# boost-demux_v1_1.net
KiCad netlist of a schematic drawn in EAGLE
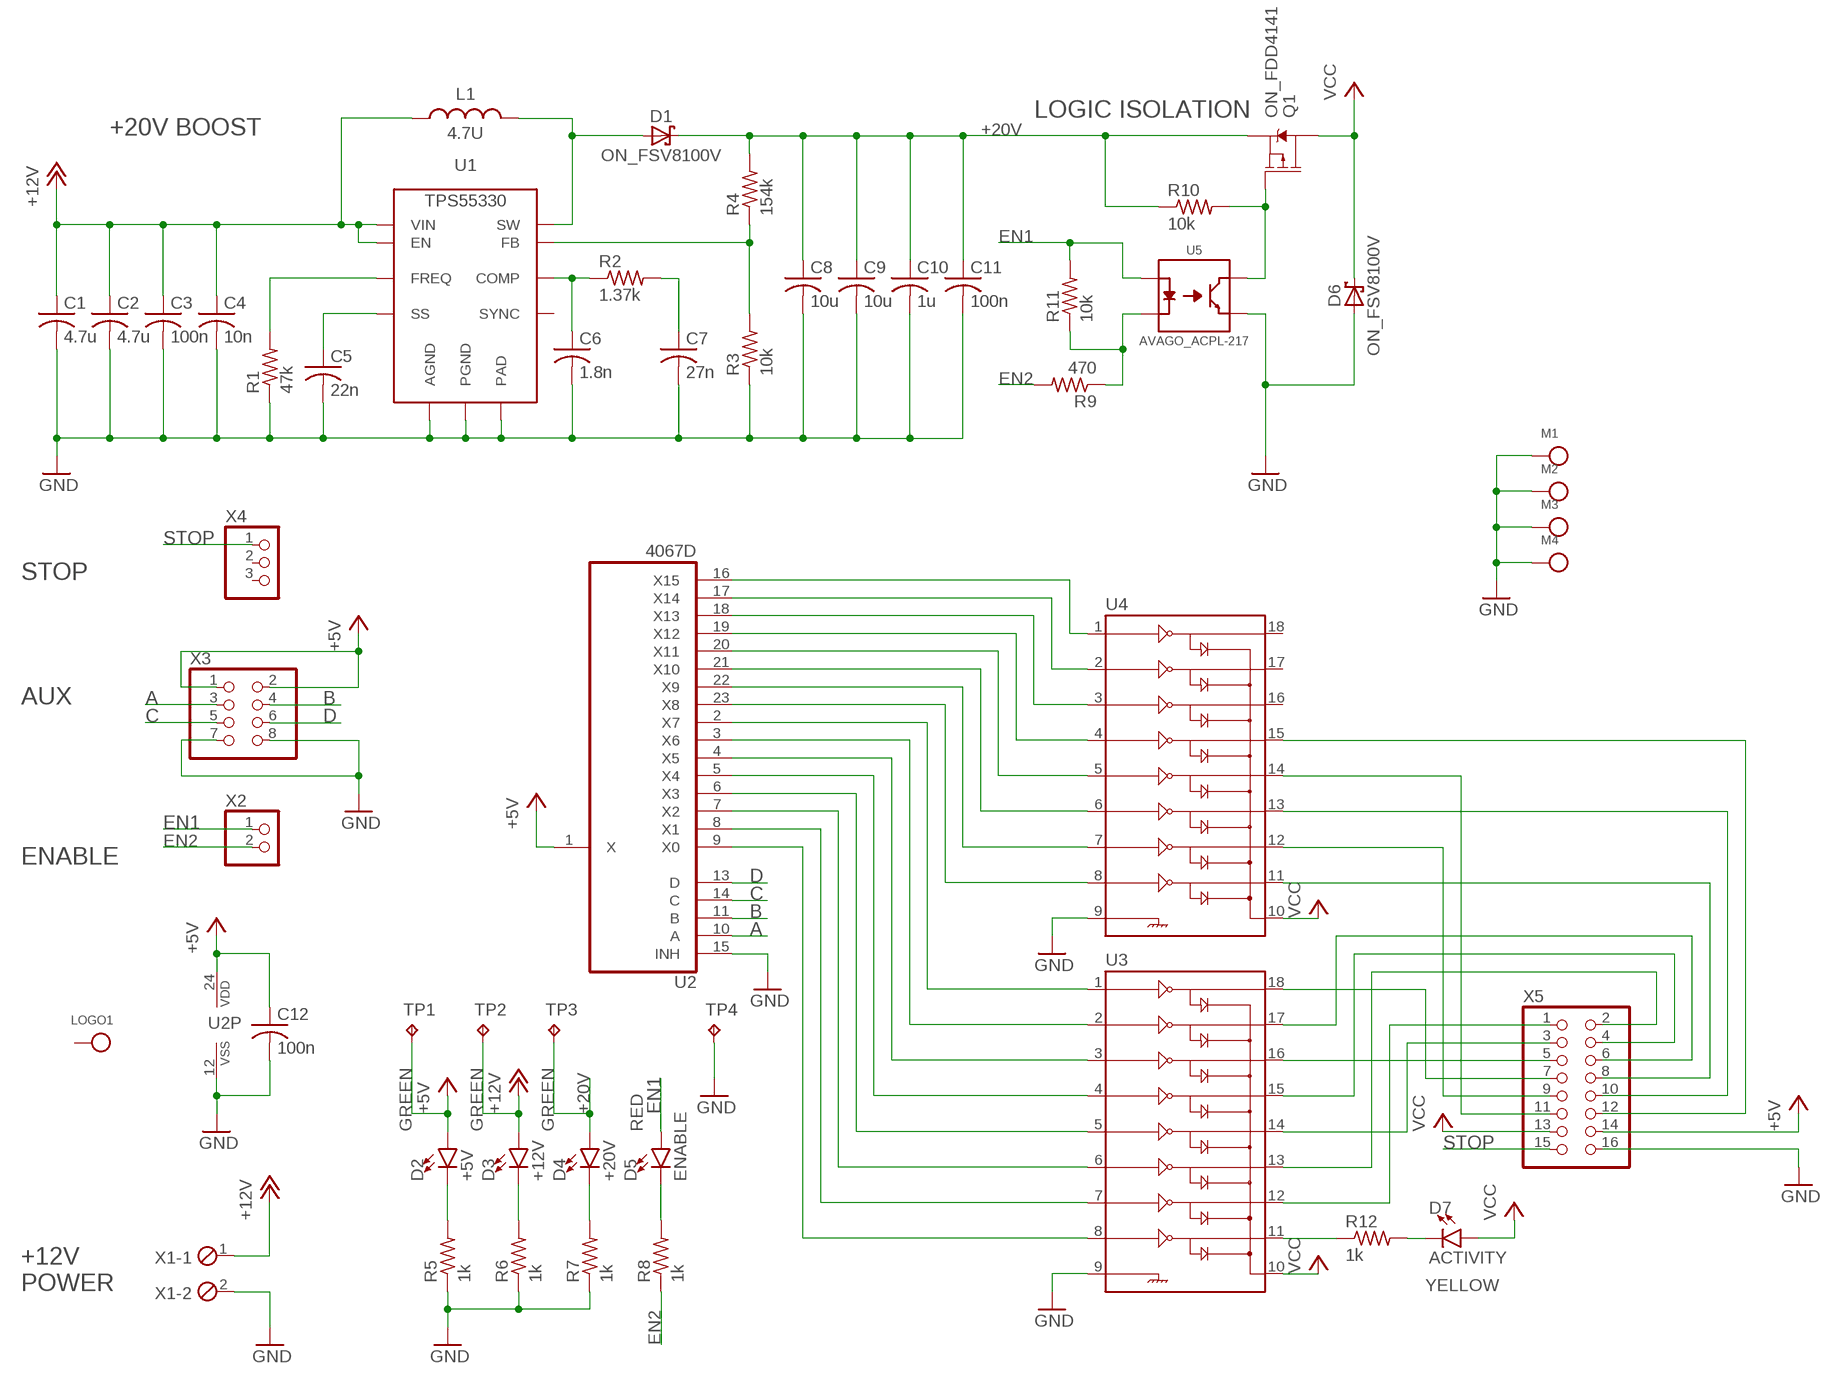
[diagram p0: schematic, sheet 1]

(export (version "E")
  (design (tool "Eeschema 10.0.6"))
  (components
    (comp (ref "C1")
      (value "4.7u")
      (footprint "eagle-import:C1206")
      (libsource (lib "eagle-import") (part "C-USC1206"))
    )
    (comp (ref "C2")
      (value "4.7u")
      (footprint "eagle-import:C1206")
      (libsource (lib "eagle-import") (part "C-USC1206"))
    )
    (comp (ref "C3")
      (value "100n")
      (footprint "eagle-import:C1206")
      (libsource (lib "eagle-import") (part "C-USC1206"))
    )
    (comp (ref "C4")
      (value "10n")
      (footprint "eagle-import:C1206")
      (libsource (lib "eagle-import") (part "C-USC1206"))
    )
    (comp (ref "C5")
      (value "22n")
      (footprint "eagle-import:C1206")
      (libsource (lib "eagle-import") (part "C-USC1206"))
    )
    (comp (ref "C6")
      (value "1.8n")
      (footprint "eagle-import:C0805")
      (libsource (lib "eagle-import") (part "C-USC0805"))
    )
    (comp (ref "C7")
      (value "27n")
      (footprint "eagle-import:C0805")
      (libsource (lib "eagle-import") (part "C-USC0805"))
    )
    (comp (ref "C8")
      (value "10u")
      (footprint "eagle-import:C1206")
      (libsource (lib "eagle-import") (part "C-USC1206"))
    )
    (comp (ref "C9")
      (value "10u")
      (footprint "eagle-import:C1206")
      (libsource (lib "eagle-import") (part "C-USC1206"))
    )
    (comp (ref "C10")
      (value "1u")
      (footprint "eagle-import:C1206")
      (libsource (lib "eagle-import") (part "C-USC1206"))
    )
    (comp (ref "C11")
      (value "100n")
      (footprint "eagle-import:C1206")
      (libsource (lib "eagle-import") (part "C-USC1206"))
    )
    (comp (ref "C12")
      (value "100n")
      (footprint "eagle-import:C1206")
      (libsource (lib "eagle-import") (part "C-USC1206"))
    )
    (comp (ref "D1")
      (value "ON_FSV8100V")
      (footprint "eagle-import:TO-277-3")
      (libsource (lib "eagle-import") (part "ON_FSV8100V"))
    )
    (comp (ref "D2")
      (value "+5V")
      (footprint "eagle-import:LED_5MM")
      (libsource (lib "eagle-import") (part "LED5MM"))
    )
    (comp (ref "D3")
      (value "+12V")
      (footprint "eagle-import:LED_5MM")
      (libsource (lib "eagle-import") (part "LED5MM"))
    )
    (comp (ref "D4")
      (value "+20V")
      (footprint "eagle-import:LED_5MM")
      (libsource (lib "eagle-import") (part "LED5MM"))
    )
    (comp (ref "D5")
      (value "ENABLE")
      (footprint "eagle-import:LED_5MM")
      (libsource (lib "eagle-import") (part "LED5MM"))
    )
    (comp (ref "D6")
      (value "ON_FSV8100V")
      (footprint "eagle-import:TO-277-3")
      (libsource (lib "eagle-import") (part "ON_FSV8100V"))
    )
    (comp (ref "D7")
      (value "ACTIVITY")
      (footprint "eagle-import:LED_5MM")
      (libsource (lib "eagle-import") (part "LED5MM"))
    )
    (comp (ref "L1")
      (value "4.7U")
      (footprint "eagle-import:4440")
      (libsource (lib "eagle-import") (part "MURATA_FDVE1040"))
    )
    (comp (ref "LOGO1")
      (value "MADOG")
      (footprint "eagle-import:MADOG")
      (libsource (lib "eagle-import") (part "MADOG"))
    )
    (comp (ref "M1")
      (value "6-32_MOUNT")
      (footprint "eagle-import:6-32_MOUNT")
      (libsource (lib "eagle-import") (part "6-32_MOUNT"))
    )
    (comp (ref "M2")
      (value "6-32_MOUNT")
      (footprint "eagle-import:6-32_MOUNT")
      (libsource (lib "eagle-import") (part "6-32_MOUNT"))
    )
    (comp (ref "M3")
      (value "6-32_MOUNT")
      (footprint "eagle-import:6-32_MOUNT")
      (libsource (lib "eagle-import") (part "6-32_MOUNT"))
    )
    (comp (ref "M4")
      (value "6-32_MOUNT")
      (footprint "eagle-import:6-32_MOUNT")
      (libsource (lib "eagle-import") (part "6-32_MOUNT"))
    )
    (comp (ref "Q1")
      (value "ON_FDD4141")
      (footprint "eagle-import:TO-252-3")
      (libsource (lib "eagle-import") (part "ON_FDD4141"))
    )
    (comp (ref "R1")
      (value "47k")
      (footprint "eagle-import:R1206")
      (libsource (lib "eagle-import") (part "R-US_R1206"))
    )
    (comp (ref "R2")
      (value "1.37k")
      (footprint "eagle-import:R0805")
      (libsource (lib "eagle-import") (part "R-US_R0805"))
    )
    (comp (ref "R3")
      (value "10k")
      (footprint "eagle-import:R0805")
      (libsource (lib "eagle-import") (part "R-US_R0805"))
    )
    (comp (ref "R4")
      (value "154k")
      (footprint "eagle-import:R0805")
      (libsource (lib "eagle-import") (part "R-US_R0805"))
    )
    (comp (ref "R5")
      (value "1k")
      (footprint "eagle-import:R1206")
      (libsource (lib "eagle-import") (part "resistor_348_R-US_R1206"))
    )
    (comp (ref "R6")
      (value "1k")
      (footprint "eagle-import:R1206")
      (libsource (lib "eagle-import") (part "resistor_348_R-US_R1206"))
    )
    (comp (ref "R7")
      (value "1k")
      (footprint "eagle-import:R1206")
      (libsource (lib "eagle-import") (part "resistor_348_R-US_R1206"))
    )
    (comp (ref "R8")
      (value "1k")
      (footprint "eagle-import:R1206")
      (libsource (lib "eagle-import") (part "resistor_348_R-US_R1206"))
    )
    (comp (ref "R9")
      (value "470")
      (footprint "eagle-import:R1206")
      (libsource (lib "eagle-import") (part "resistor_348_R-US_R1206"))
    )
    (comp (ref "R10")
      (value "10k")
      (footprint "eagle-import:R0805")
      (libsource (lib "eagle-import") (part "R-US_R0805"))
    )
    (comp (ref "R11")
      (value "10k")
      (footprint "eagle-import:R0805")
      (libsource (lib "eagle-import") (part "R-US_R0805"))
    )
    (comp (ref "R12")
      (value "1k")
      (footprint "eagle-import:R1206")
      (libsource (lib "eagle-import") (part "resistor_348_R-US_R1206"))
    )
    (comp (ref "TP1")
      (value "TPB1,27")
      (footprint "eagle-import:B1,27")
      (libsource (lib "eagle-import") (part "TPB1,27"))
    )
    (comp (ref "TP2")
      (value "TPB1,27")
      (footprint "eagle-import:B1,27")
      (libsource (lib "eagle-import") (part "TPB1,27"))
    )
    (comp (ref "TP3")
      (value "TPB1,27")
      (footprint "eagle-import:B1,27")
      (libsource (lib "eagle-import") (part "TPB1,27"))
    )
    (comp (ref "TP4")
      (value "TPB1,27")
      (footprint "eagle-import:B1,27")
      (libsource (lib "eagle-import") (part "TPB1,27"))
    )
    (comp (ref "U1")
      (value "TI_TPS55330")
      (footprint "eagle-import:S-PWQFN-N16")
      (libsource (lib "eagle-import") (part "TI_TPS55330"))
    )
    (comp (ref "U2")
      (value "4067D")
      (footprint "eagle-import:SO24W")
      (libsource (lib "eagle-import") (part "4067D"))
    )
    (comp (ref "U3")
      (value "ULN2803SOICW")
      (footprint "eagle-import:SO18L")
      (libsource (lib "eagle-import") (part "ULN2803SOICW"))
    )
    (comp (ref "U4")
      (value "ULN2803SOICW")
      (footprint "eagle-import:SO18L")
      (libsource (lib "eagle-import") (part "ULN2803SOICW"))
    )
    (comp (ref "U5")
      (value "AVAGO_ACPL-217")
      (footprint "eagle-import:SOIC-4")
      (libsource (lib "eagle-import") (part "AVAGO_ACPL-217"))
    )
    (comp (ref "X1")
      (value "MPT2")
      (footprint "eagle-import:2POL254")
      (libsource (lib "eagle-import") (part "MPT2"))
    )
    (comp (ref "X2")
      (value "PINHD-1X2/90")
      (footprint "eagle-import:1X02_90")
      (libsource (lib "eagle-import") (part "PINHD-1X2/90"))
    )
    (comp (ref "X3")
      (value "PINHD-2X4/90")
      (footprint "eagle-import:2X04_90")
      (libsource (lib "eagle-import") (part "PINHD-2X4/90"))
    )
    (comp (ref "X4")
      (value "PINHD-1X3/90")
      (footprint "eagle-import:1X03_90")
      (libsource (lib "eagle-import") (part "PINHD-1X3/90"))
    )
    (comp (ref "X5")
      (value "PINHD-2X8")
      (footprint "eagle-import:2X08")
      (libsource (lib "eagle-import") (part "PINHD-2X8"))
    )
  )
  (nets
    (net (code "1") (name "+5V") (class "Default")
      (node (ref "C12") (pin "1") (pinfunction "1_1") (pintype "passive"))
      (node (ref "D2") (pin "A") (pinfunction "A_A") (pintype "passive"))
      (node (ref "TP1") (pin "TP") (pinfunction "TP_TP") (pintype "input"))
      (node (ref "U2") (pin "1") (pinfunction "X_1") (pintype "output"))
      (node (ref "U2") (pin "24") (pinfunction "VDD_24") (pintype "power_in"))
      (node (ref "X3") (pin "1") (pinfunction "1_1") (pintype "passive"))
      (node (ref "X3") (pin "2") (pinfunction "2_2") (pintype "passive"))
      (node (ref "X5") (pin "14") (pinfunction "14_14") (pintype "passive"))
    )
    (net (code "2") (name "+12V") (class "Default")
      (node (ref "C1") (pin "1") (pinfunction "1_1") (pintype "passive"))
      (node (ref "C2") (pin "1") (pinfunction "1_1") (pintype "passive"))
      (node (ref "C3") (pin "1") (pinfunction "1_1") (pintype "passive"))
      (node (ref "C4") (pin "1") (pinfunction "1_1") (pintype "passive"))
      (node (ref "D3") (pin "A") (pinfunction "A_A") (pintype "passive"))
      (node (ref "L1") (pin "1") (pinfunction "1_1") (pintype "passive"))
      (node (ref "TP2") (pin "TP") (pinfunction "TP_TP") (pintype "input"))
      (node (ref "U1") (pin "2") (pinfunction "VIN_2") (pintype "passive"))
      (node (ref "U1") (pin "3") (pinfunction "EN_3") (pintype "passive"))
      (node (ref "X1") (pin "1") (pinfunction "1_1") (pintype "passive"))
    )
    (net (code "3") (name "/+20V") (class "Default")
      (node (ref "C10") (pin "1") (pinfunction "1_1") (pintype "passive"))
      (node (ref "C11") (pin "1") (pinfunction "1_1") (pintype "passive"))
      (node (ref "C8") (pin "1") (pinfunction "1_1") (pintype "passive"))
      (node (ref "C9") (pin "1") (pinfunction "1_1") (pintype "passive"))
      (node (ref "D1") (pin "P$3") (pinfunction "C_P$3") (pintype "passive"))
      (node (ref "D4") (pin "A") (pinfunction "A_A") (pintype "passive"))
      (node (ref "Q1") (pin "P$3") (pinfunction "S_P$3") (pintype "bidirectional"))
      (node (ref "R10") (pin "1") (pinfunction "1_1") (pintype "passive"))
      (node (ref "R4") (pin "2") (pinfunction "2_2") (pintype "passive"))
      (node (ref "TP3") (pin "TP") (pinfunction "TP_TP") (pintype "input"))
    )
    (net (code "4") (name "/A") (class "Default")
      (node (ref "U2") (pin "10") (pinfunction "A_10") (pintype "input"))
      (node (ref "X3") (pin "3") (pinfunction "3_3") (pintype "passive"))
    )
    (net (code "5") (name "/B") (class "Default")
      (node (ref "U2") (pin "11") (pinfunction "B_11") (pintype "input"))
      (node (ref "X3") (pin "4") (pinfunction "4_4") (pintype "passive"))
    )
    (net (code "6") (name "/C") (class "Default")
      (node (ref "U2") (pin "14") (pinfunction "C_14") (pintype "input"))
      (node (ref "X3") (pin "5") (pinfunction "5_5") (pintype "passive"))
    )
    (net (code "7") (name "/D") (class "Default")
      (node (ref "U2") (pin "13") (pinfunction "D_13") (pintype "input"))
      (node (ref "X3") (pin "6") (pinfunction "6_6") (pintype "passive"))
    )
    (net (code "8") (name "/EN1") (class "Default")
      (node (ref "D5") (pin "A") (pinfunction "A_A") (pintype "passive"))
      (node (ref "R11") (pin "2") (pinfunction "2_2") (pintype "passive"))
      (node (ref "U5") (pin "P$1") (pinfunction "P$1_P$1") (pintype "bidirectional"))
      (node (ref "X2") (pin "1") (pinfunction "1_1") (pintype "passive"))
    )
    (net (code "9") (name "/EN2") (class "Default")
      (node (ref "R8") (pin "1") (pinfunction "1_1") (pintype "passive"))
      (node (ref "R9") (pin "2") (pinfunction "2_2") (pintype "passive"))
      (node (ref "X2") (pin "2") (pinfunction "2_2") (pintype "passive"))
    )
    (net (code "10") (name "/STOP") (class "Default")
      (node (ref "X4") (pin "1") (pinfunction "1_1") (pintype "passive"))
      (node (ref "X5") (pin "15") (pinfunction "15_15") (pintype "passive"))
    )
    (net (code "11") (name "GND") (class "Default")
      (node (ref "C1") (pin "2") (pinfunction "2_2") (pintype "passive"))
      (node (ref "C10") (pin "2") (pinfunction "2_2") (pintype "passive"))
      (node (ref "C11") (pin "2") (pinfunction "2_2") (pintype "passive"))
      (node (ref "C12") (pin "2") (pinfunction "2_2") (pintype "passive"))
      (node (ref "C2") (pin "2") (pinfunction "2_2") (pintype "passive"))
      (node (ref "C3") (pin "2") (pinfunction "2_2") (pintype "passive"))
      (node (ref "C4") (pin "2") (pinfunction "2_2") (pintype "passive"))
      (node (ref "C5") (pin "2") (pinfunction "2_2") (pintype "passive"))
      (node (ref "C6") (pin "2") (pinfunction "2_2") (pintype "passive"))
      (node (ref "C7") (pin "2") (pinfunction "2_2") (pintype "passive"))
      (node (ref "C8") (pin "2") (pinfunction "2_2") (pintype "passive"))
      (node (ref "C9") (pin "2") (pinfunction "2_2") (pintype "passive"))
      (node (ref "D6") (pin "P$1") (pinfunction "A_P$1") (pintype "passive"))
      (node (ref "D6") (pin "P$2") (pinfunction "A_P$2") (pintype "passive"))
      (node (ref "M1") (pin "P$1") (pinfunction "P$1_P$1") (pintype "bidirectional"))
      (node (ref "M1") (pin "P$2") (pinfunction "P$1_P$2") (pintype "bidirectional"))
      (node (ref "M1") (pin "P$3") (pinfunction "P$1_P$3") (pintype "bidirectional"))
      (node (ref "M1") (pin "P$4") (pinfunction "P$1_P$4") (pintype "bidirectional"))
      (node (ref "M1") (pin "P$5") (pinfunction "P$1_P$5") (pintype "bidirectional"))
      (node (ref "M1") (pin "P$6") (pinfunction "P$1_P$6") (pintype "bidirectional"))
      (node (ref "M1") (pin "P$7") (pinfunction "P$1_P$7") (pintype "bidirectional"))
      (node (ref "M1") (pin "P$8") (pinfunction "P$1_P$8") (pintype "bidirectional"))
      (node (ref "M1") (pin "P$9") (pinfunction "P$1_P$9") (pintype "bidirectional"))
      (node (ref "M2") (pin "P$1") (pinfunction "P$1_P$1") (pintype "bidirectional"))
      (node (ref "M2") (pin "P$2") (pinfunction "P$1_P$2") (pintype "bidirectional"))
      (node (ref "M2") (pin "P$3") (pinfunction "P$1_P$3") (pintype "bidirectional"))
      (node (ref "M2") (pin "P$4") (pinfunction "P$1_P$4") (pintype "bidirectional"))
      (node (ref "M2") (pin "P$5") (pinfunction "P$1_P$5") (pintype "bidirectional"))
      (node (ref "M2") (pin "P$6") (pinfunction "P$1_P$6") (pintype "bidirectional"))
      (node (ref "M2") (pin "P$7") (pinfunction "P$1_P$7") (pintype "bidirectional"))
      (node (ref "M2") (pin "P$8") (pinfunction "P$1_P$8") (pintype "bidirectional"))
      (node (ref "M2") (pin "P$9") (pinfunction "P$1_P$9") (pintype "bidirectional"))
      (node (ref "M3") (pin "P$1") (pinfunction "P$1_P$1") (pintype "bidirectional"))
      (node (ref "M3") (pin "P$2") (pinfunction "P$1_P$2") (pintype "bidirectional"))
      (node (ref "M3") (pin "P$3") (pinfunction "P$1_P$3") (pintype "bidirectional"))
      (node (ref "M3") (pin "P$4") (pinfunction "P$1_P$4") (pintype "bidirectional"))
      (node (ref "M3") (pin "P$5") (pinfunction "P$1_P$5") (pintype "bidirectional"))
      (node (ref "M3") (pin "P$6") (pinfunction "P$1_P$6") (pintype "bidirectional"))
      (node (ref "M3") (pin "P$7") (pinfunction "P$1_P$7") (pintype "bidirectional"))
      (node (ref "M3") (pin "P$8") (pinfunction "P$1_P$8") (pintype "bidirectional"))
      (node (ref "M3") (pin "P$9") (pinfunction "P$1_P$9") (pintype "bidirectional"))
      (node (ref "M4") (pin "P$1") (pinfunction "P$1_P$1") (pintype "bidirectional"))
      (node (ref "M4") (pin "P$2") (pinfunction "P$1_P$2") (pintype "bidirectional"))
      (node (ref "M4") (pin "P$3") (pinfunction "P$1_P$3") (pintype "bidirectional"))
      (node (ref "M4") (pin "P$4") (pinfunction "P$1_P$4") (pintype "bidirectional"))
      (node (ref "M4") (pin "P$5") (pinfunction "P$1_P$5") (pintype "bidirectional"))
      (node (ref "M4") (pin "P$6") (pinfunction "P$1_P$6") (pintype "bidirectional"))
      (node (ref "M4") (pin "P$7") (pinfunction "P$1_P$7") (pintype "bidirectional"))
      (node (ref "M4") (pin "P$8") (pinfunction "P$1_P$8") (pintype "bidirectional"))
      (node (ref "M4") (pin "P$9") (pinfunction "P$1_P$9") (pintype "bidirectional"))
      (node (ref "R1") (pin "1") (pinfunction "1_1") (pintype "passive"))
      (node (ref "R3") (pin "1") (pinfunction "1_1") (pintype "passive"))
      (node (ref "R5") (pin "1") (pinfunction "1_1") (pintype "passive"))
      (node (ref "R6") (pin "1") (pinfunction "1_1") (pintype "passive"))
      (node (ref "R7") (pin "1") (pinfunction "1_1") (pintype "passive"))
      (node (ref "TP4") (pin "TP") (pinfunction "TP_TP") (pintype "input"))
      (node (ref "U1") (pin "11") (pinfunction "PGND_11") (pintype "passive"))
      (node (ref "U1") (pin "12") (pinfunction "PGND_12") (pintype "passive"))
      (node (ref "U1") (pin "13") (pinfunction "PGND_13") (pintype "passive"))
      (node (ref "U1") (pin "6") (pinfunction "AGND_6") (pintype "passive"))
      (node (ref "U1") (pin "PAD") (pinfunction "PAD_PAD") (pintype "bidirectional"))
      (node (ref "U2") (pin "12") (pinfunction "VSS_12") (pintype "power_in"))
      (node (ref "U2") (pin "15") (pinfunction "INH_15") (pintype "input"))
      (node (ref "U3") (pin "9") (pinfunction "9_9") (pintype "bidirectional"))
      (node (ref "U4") (pin "9") (pinfunction "9_9") (pintype "bidirectional"))
      (node (ref "U5") (pin "P$3") (pinfunction "P$3_P$3") (pintype "bidirectional"))
      (node (ref "X1") (pin "2") (pinfunction "1_2") (pintype "passive"))
      (node (ref "X3") (pin "7") (pinfunction "7_7") (pintype "passive"))
      (node (ref "X3") (pin "8") (pinfunction "8_8") (pintype "passive"))
      (node (ref "X5") (pin "16") (pinfunction "16_16") (pintype "passive"))
    )
    (net (code "12") (name "Net-(C7-Pad1)") (class "Default")
      (node (ref "C7") (pin "1") (pinfunction "1_1") (pintype "passive"))
      (node (ref "R2") (pin "2") (pinfunction "2_2") (pintype "passive"))
    )
    (net (code "13") (name "Net-(D1-A-PadP$1)") (class "Default")
      (node (ref "D1") (pin "P$1") (pinfunction "A_P$1") (pintype "passive"))
      (node (ref "D1") (pin "P$2") (pinfunction "A_P$2") (pintype "passive"))
      (node (ref "L1") (pin "2") (pinfunction "2_2") (pintype "passive"))
      (node (ref "U1") (pin "1") (pinfunction "SW_1") (pintype "passive"))
      (node (ref "U1") (pin "15") (pinfunction "SW_15") (pintype "passive"))
      (node (ref "U1") (pin "16") (pinfunction "SW_16") (pintype "passive"))
    )
    (net (code "14") (name "Net-(D2-C)") (class "Default")
      (node (ref "D2") (pin "K") (pinfunction "C_K") (pintype "passive"))
      (node (ref "R5") (pin "2") (pinfunction "2_2") (pintype "passive"))
    )
    (net (code "15") (name "Net-(D3-C)") (class "Default")
      (node (ref "D3") (pin "K") (pinfunction "C_K") (pintype "passive"))
      (node (ref "R6") (pin "2") (pinfunction "2_2") (pintype "passive"))
    )
    (net (code "16") (name "Net-(D4-C)") (class "Default")
      (node (ref "D4") (pin "K") (pinfunction "C_K") (pintype "passive"))
      (node (ref "R7") (pin "2") (pinfunction "2_2") (pintype "passive"))
    )
    (net (code "17") (name "Net-(D5-C)") (class "Default")
      (node (ref "D5") (pin "K") (pinfunction "C_K") (pintype "passive"))
      (node (ref "R8") (pin "2") (pinfunction "2_2") (pintype "passive"))
    )
    (net (code "18") (name "Net-(D7-C)") (class "Default")
      (node (ref "D7") (pin "K") (pinfunction "C_K") (pintype "passive"))
      (node (ref "R12") (pin "2") (pinfunction "2_2") (pintype "passive"))
    )
    (net (code "19") (name "Net-(Q1-G)") (class "Default")
      (node (ref "Q1") (pin "P$1") (pinfunction "G_P$1") (pintype "bidirectional"))
      (node (ref "R10") (pin "2") (pinfunction "2_2") (pintype "passive"))
      (node (ref "U5") (pin "P$4") (pinfunction "P$4_P$4") (pintype "bidirectional"))
    )
    (net (code "20") (name "Net-(R11-Pad1)") (class "Default")
      (node (ref "R11") (pin "1") (pinfunction "1_1") (pintype "passive"))
      (node (ref "R9") (pin "1") (pinfunction "1_1") (pintype "passive"))
      (node (ref "U5") (pin "P$2") (pinfunction "P$2_P$2") (pintype "bidirectional"))
    )
    (net (code "21") (name "Net-(R12-Pad1)") (class "Default")
      (node (ref "R12") (pin "1") (pinfunction "1_1") (pintype "passive"))
      (node (ref "U3") (pin "11") (pinfunction "11_11") (pintype "bidirectional"))
    )
    (net (code "22") (name "Net-(U1-COMP)") (class "Default")
      (node (ref "C6") (pin "1") (pinfunction "1_1") (pintype "passive"))
      (node (ref "R2") (pin "1") (pinfunction "1_1") (pintype "passive"))
      (node (ref "U1") (pin "7") (pinfunction "COMP_7") (pintype "passive"))
    )
    (net (code "23") (name "Net-(U1-FB)") (class "Default")
      (node (ref "R3") (pin "2") (pinfunction "2_2") (pintype "passive"))
      (node (ref "R4") (pin "1") (pinfunction "1_1") (pintype "passive"))
      (node (ref "U1") (pin "8") (pinfunction "FB_8") (pintype "passive"))
    )
    (net (code "24") (name "Net-(U1-FREQ)") (class "Default")
      (node (ref "R1") (pin "2") (pinfunction "2_2") (pintype "passive"))
      (node (ref "U1") (pin "9") (pinfunction "FREQ_9") (pintype "passive"))
    )
    (net (code "25") (name "Net-(U1-SS)") (class "Default")
      (node (ref "C5") (pin "1") (pinfunction "1_1") (pintype "passive"))
      (node (ref "U1") (pin "4") (pinfunction "SS_4") (pintype "passive"))
    )
    (net (code "26") (name "Net-(U2A-X0)") (class "Default")
      (node (ref "U2") (pin "9") (pinfunction "X0_9") (pintype "input"))
      (node (ref "U3") (pin "8") (pinfunction "8_8") (pintype "bidirectional"))
    )
    (net (code "27") (name "Net-(U2A-X1)") (class "Default")
      (node (ref "U2") (pin "8") (pinfunction "X1_8") (pintype "input"))
      (node (ref "U3") (pin "7") (pinfunction "7_7") (pintype "bidirectional"))
    )
    (net (code "28") (name "Net-(U2A-X2)") (class "Default")
      (node (ref "U2") (pin "7") (pinfunction "X2_7") (pintype "input"))
      (node (ref "U3") (pin "6") (pinfunction "6_6") (pintype "bidirectional"))
    )
    (net (code "29") (name "Net-(U2A-X3)") (class "Default")
      (node (ref "U2") (pin "6") (pinfunction "X3_6") (pintype "input"))
      (node (ref "U3") (pin "5") (pinfunction "5_5") (pintype "bidirectional"))
    )
    (net (code "30") (name "Net-(U2A-X4)") (class "Default")
      (node (ref "U2") (pin "5") (pinfunction "X4_5") (pintype "input"))
      (node (ref "U3") (pin "4") (pinfunction "4_4") (pintype "bidirectional"))
    )
    (net (code "31") (name "Net-(U2A-X5)") (class "Default")
      (node (ref "U2") (pin "4") (pinfunction "X5_4") (pintype "input"))
      (node (ref "U3") (pin "3") (pinfunction "3_3") (pintype "bidirectional"))
    )
    (net (code "32") (name "Net-(U2A-X6)") (class "Default")
      (node (ref "U2") (pin "3") (pinfunction "X6_3") (pintype "input"))
      (node (ref "U3") (pin "2") (pinfunction "2_2") (pintype "bidirectional"))
    )
    (net (code "33") (name "Net-(U2A-X7)") (class "Default")
      (node (ref "U2") (pin "2") (pinfunction "X7_2") (pintype "input"))
      (node (ref "U3") (pin "1") (pinfunction "1_1") (pintype "bidirectional"))
    )
    (net (code "34") (name "Net-(U2A-X8)") (class "Default")
      (node (ref "U2") (pin "23") (pinfunction "X8_23") (pintype "input"))
      (node (ref "U4") (pin "8") (pinfunction "8_8") (pintype "bidirectional"))
    )
    (net (code "35") (name "Net-(U2A-X9)") (class "Default")
      (node (ref "U2") (pin "22") (pinfunction "X9_22") (pintype "input"))
      (node (ref "U4") (pin "7") (pinfunction "7_7") (pintype "bidirectional"))
    )
    (net (code "36") (name "Net-(U2A-X10)") (class "Default")
      (node (ref "U2") (pin "21") (pinfunction "X10_21") (pintype "input"))
      (node (ref "U4") (pin "6") (pinfunction "6_6") (pintype "bidirectional"))
    )
    (net (code "37") (name "Net-(U2A-X11)") (class "Default")
      (node (ref "U2") (pin "20") (pinfunction "X11_20") (pintype "input"))
      (node (ref "U4") (pin "5") (pinfunction "5_5") (pintype "bidirectional"))
    )
    (net (code "38") (name "Net-(U2A-X12)") (class "Default")
      (node (ref "U2") (pin "19") (pinfunction "X12_19") (pintype "input"))
      (node (ref "U4") (pin "4") (pinfunction "4_4") (pintype "bidirectional"))
    )
    (net (code "39") (name "Net-(U2A-X13)") (class "Default")
      (node (ref "U2") (pin "18") (pinfunction "X13_18") (pintype "input"))
      (node (ref "U4") (pin "3") (pinfunction "3_3") (pintype "bidirectional"))
    )
    (net (code "40") (name "Net-(U2A-X14)") (class "Default")
      (node (ref "U2") (pin "17") (pinfunction "X14_17") (pintype "input"))
      (node (ref "U4") (pin "2") (pinfunction "2_2") (pintype "bidirectional"))
    )
    (net (code "41") (name "Net-(U2A-X15)") (class "Default")
      (node (ref "U2") (pin "16") (pinfunction "X15_16") (pintype "input"))
      (node (ref "U4") (pin "1") (pinfunction "1_1") (pintype "bidirectional"))
    )
    (net (code "42") (name "Net-(U3-Pad12)") (class "Default")
      (node (ref "U3") (pin "12") (pinfunction "12_12") (pintype "bidirectional"))
      (node (ref "X5") (pin "1") (pinfunction "1_1") (pintype "passive"))
    )
    (net (code "43") (name "Net-(U3-Pad13)") (class "Default")
      (node (ref "U3") (pin "13") (pinfunction "13_13") (pintype "bidirectional"))
      (node (ref "X5") (pin "2") (pinfunction "2_2") (pintype "passive"))
    )
    (net (code "44") (name "Net-(U3-Pad14)") (class "Default")
      (node (ref "U3") (pin "14") (pinfunction "14_14") (pintype "bidirectional"))
      (node (ref "X5") (pin "3") (pinfunction "3_3") (pintype "passive"))
    )
    (net (code "45") (name "Net-(U3-Pad15)") (class "Default")
      (node (ref "U3") (pin "15") (pinfunction "15_15") (pintype "bidirectional"))
      (node (ref "X5") (pin "4") (pinfunction "4_4") (pintype "passive"))
    )
    (net (code "46") (name "Net-(U3-Pad16)") (class "Default")
      (node (ref "U3") (pin "16") (pinfunction "16_16") (pintype "bidirectional"))
      (node (ref "X5") (pin "5") (pinfunction "5_5") (pintype "passive"))
    )
    (net (code "47") (name "Net-(U3-Pad17)") (class "Default")
      (node (ref "U3") (pin "17") (pinfunction "17_17") (pintype "bidirectional"))
      (node (ref "X5") (pin "6") (pinfunction "6_6") (pintype "passive"))
    )
    (net (code "48") (name "Net-(U3-Pad18)") (class "Default")
      (node (ref "U3") (pin "18") (pinfunction "18_18") (pintype "bidirectional"))
      (node (ref "X5") (pin "7") (pinfunction "7_7") (pintype "passive"))
    )
    (net (code "49") (name "Net-(U4-Pad11)") (class "Default")
      (node (ref "U4") (pin "11") (pinfunction "11_11") (pintype "bidirectional"))
      (node (ref "X5") (pin "8") (pinfunction "8_8") (pintype "passive"))
    )
    (net (code "50") (name "Net-(U4-Pad12)") (class "Default")
      (node (ref "U4") (pin "12") (pinfunction "12_12") (pintype "bidirectional"))
      (node (ref "X5") (pin "9") (pinfunction "9_9") (pintype "passive"))
    )
    (net (code "51") (name "Net-(U4-Pad13)") (class "Default")
      (node (ref "U4") (pin "13") (pinfunction "13_13") (pintype "bidirectional"))
      (node (ref "X5") (pin "10") (pinfunction "10_10") (pintype "passive"))
    )
    (net (code "52") (name "Net-(U4-Pad14)") (class "Default")
      (node (ref "U4") (pin "14") (pinfunction "14_14") (pintype "bidirectional"))
      (node (ref "X5") (pin "11") (pinfunction "11_11") (pintype "passive"))
    )
    (net (code "53") (name "Net-(U4-Pad15)") (class "Default")
      (node (ref "U4") (pin "15") (pinfunction "15_15") (pintype "bidirectional"))
      (node (ref "X5") (pin "12") (pinfunction "12_12") (pintype "passive"))
    )
    (net (code "54") (name "VCC") (class "Default")
      (node (ref "D6") (pin "P$3") (pinfunction "C_P$3") (pintype "passive"))
      (node (ref "D7") (pin "A") (pinfunction "A_A") (pintype "passive"))
      (node (ref "Q1") (pin "P$4") (pinfunction "D_P$4") (pintype "bidirectional"))
      (node (ref "U3") (pin "10") (pinfunction "10_10") (pintype "bidirectional"))
      (node (ref "U4") (pin "10") (pinfunction "10_10") (pintype "bidirectional"))
      (node (ref "X5") (pin "13") (pinfunction "13_13") (pintype "passive"))
    )
    (net (code "55") (name "unconnected-(LOGO1-PadP$1)") (class "Default")
      (node (ref "LOGO1") (pin "P$1") (pinfunction "P$1_P$1") (pintype "bidirectional"))
    )
    (net (code "56") (name "unconnected-(U1-SYNC-Pad5)") (class "Default")
      (node (ref "U1") (pin "5") (pinfunction "SYNC_5") (pintype "passive"))
    )
    (net (code "57") (name "unconnected-(U4-Pad16)") (class "Default")
      (node (ref "U4") (pin "16") (pinfunction "16_16") (pintype "bidirectional"))
    )
    (net (code "58") (name "unconnected-(U4-Pad17)") (class "Default")
      (node (ref "U4") (pin "17") (pinfunction "17_17") (pintype "bidirectional"))
    )
    (net (code "59") (name "unconnected-(U4-Pad18)") (class "Default")
      (node (ref "U4") (pin "18") (pinfunction "18_18") (pintype "bidirectional"))
    )
    (net (code "60") (name "unconnected-(X4-Pad2)") (class "Default")
      (node (ref "X4") (pin "2") (pinfunction "2_2") (pintype "passive"))
    )
    (net (code "61") (name "unconnected-(X4-Pad3)") (class "Default")
      (node (ref "X4") (pin "3") (pinfunction "3_3") (pintype "passive"))
    )
  )
)
